# Altium_v0_6_2.net
KiCad netlist of a schematic drawn in Altium Designer
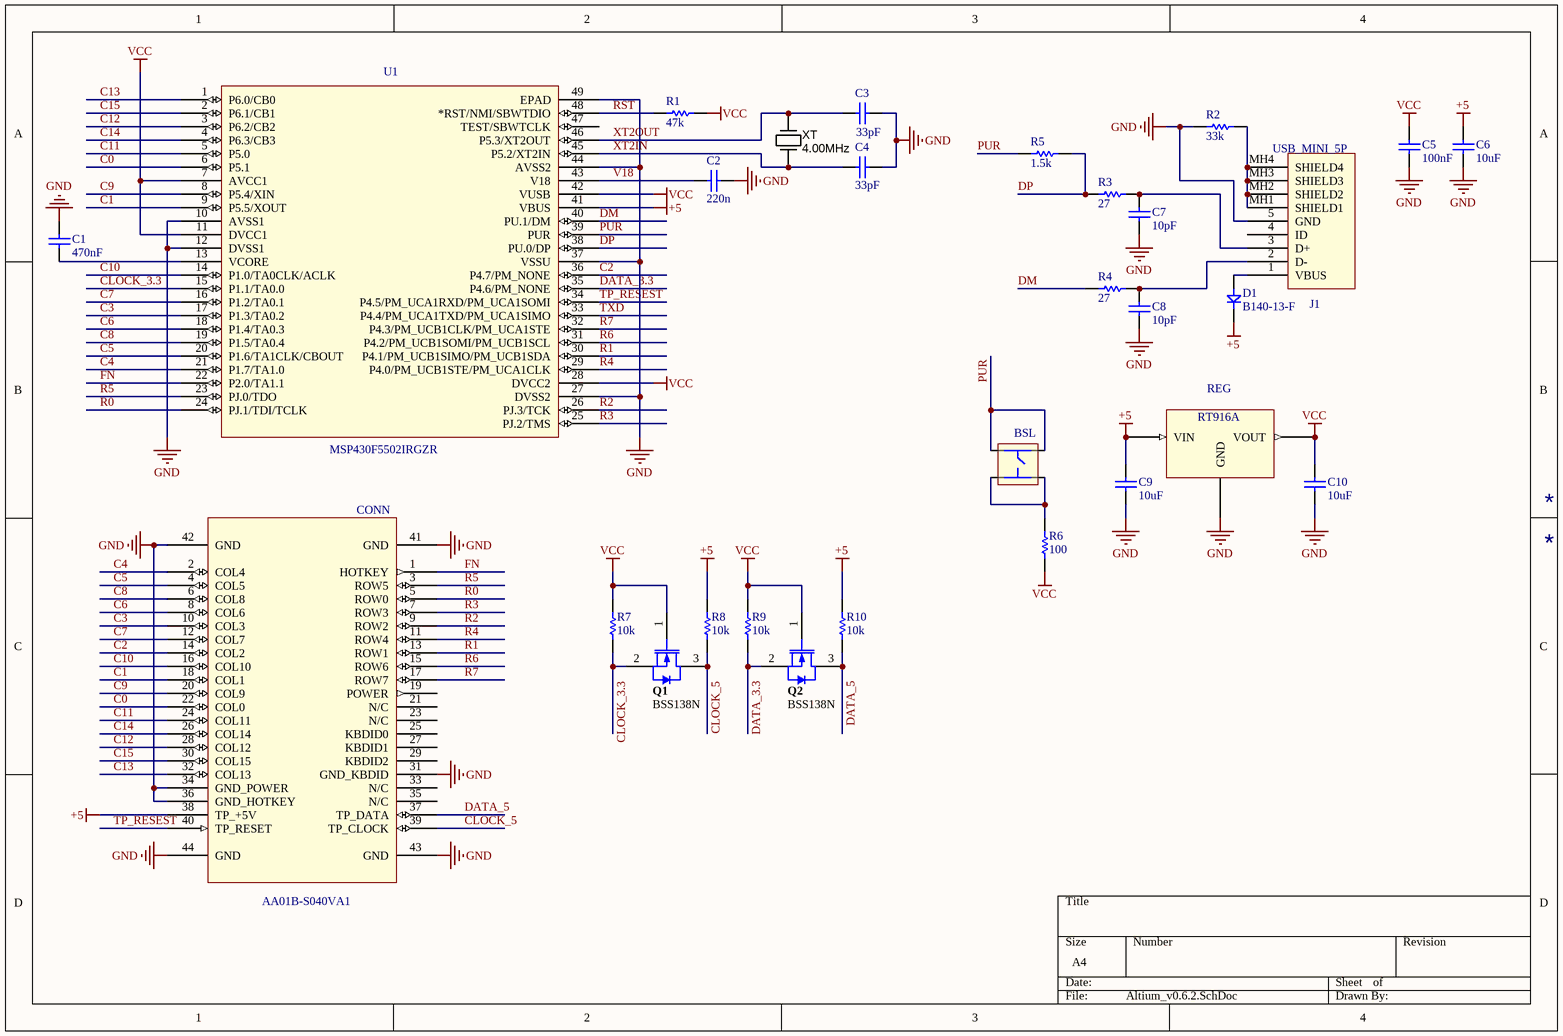
[diagram p0: Altium_v0.6.2.SchDoc]

(export (version "E")
  (design (tool "Eeschema 10.0.6"))
  (components
    (comp (ref "BSL")
      (value "TL3301")
      (footprint "TL3301")
      (description "TL3301, tactile switch, gull wing termination")
      (libsource (lib "MSP430_USB") (part "TL3301"))
    )
    (comp (ref "C1")
      (value "470nF")
      (footprint "C0805")
      (description "Capacitor")
      (fields (field (name "Comment") "Cap") (field (name "PUBLISHER") "Altium Limited"))
      (libsource (lib "Miscellaneous Devices") (part "Cap"))
    )
    (comp (ref "C2")
      (value "220n")
      (footprint "C0805")
      (description "Capacitor")
      (fields (field (name "Comment") "Cap") (field (name "PUBLISHER") "Altium Limited"))
      (libsource (lib "Miscellaneous Devices") (part "Cap"))
    )
    (comp (ref "C3")
      (value "33pF")
      (footprint "C0805")
      (description "Capacitor")
      (fields (field (name "Comment") "Cap") (field (name "PUBLISHER") "Altium Limited"))
      (libsource (lib "Miscellaneous Devices") (part "Cap"))
    )
    (comp (ref "C4")
      (value "33pF")
      (footprint "C0805")
      (description "Capacitor")
      (fields (field (name "Comment") "Cap") (field (name "PUBLISHER") "Altium Limited"))
      (libsource (lib "Miscellaneous Devices") (part "Cap"))
    )
    (comp (ref "C5")
      (value "100nF")
      (description "Capacitor")
      (fields (field (name "Comment") "Cap") (field (name "PUBLISHER") "Altium Limited"))
      (libsource (lib "Miscellaneous Devices") (part "Cap"))
    )
    (comp (ref "C6")
      (value "10uF")
      (description "Capacitor")
      (fields (field (name "Comment") "Cap") (field (name "PUBLISHER") "Altium Limited"))
      (libsource (lib "Miscellaneous Devices") (part "Cap"))
    )
    (comp (ref "C7")
      (value "10pF")
      (description "Capacitor")
      (fields (field (name "Comment") "Cap") (field (name "PUBLISHER") "Altium Limited"))
      (libsource (lib "Miscellaneous Devices") (part "Cap"))
    )
    (comp (ref "C8")
      (value "10pF")
      (description "Capacitor")
      (fields (field (name "Comment") "Cap") (field (name "PUBLISHER") "Altium Limited"))
      (libsource (lib "Miscellaneous Devices") (part "Cap"))
    )
    (comp (ref "C9")
      (value "10uF")
      (description "Capacitor")
      (fields (field (name "Comment") "Cap") (field (name "PUBLISHER") "Altium Limited"))
      (libsource (lib "Miscellaneous Devices") (part "Cap"))
    )
    (comp (ref "C10")
      (value "10uF")
      (description "Capacitor")
      (fields (field (name "Comment") "Cap") (field (name "PUBLISHER") "Altium Limited"))
      (libsource (lib "Miscellaneous Devices") (part "Cap"))
    )
    (comp (ref "CONN")
      (value "AA01B-S040VA1")
      (footprint "AA01B-S040VA1")
      (description "AA01B-S040VA1, LAPTOP KEYBOARD RECEPTACLE")
      (libsource (lib "AA01B-S040VA1") (part "AA01B-S040VA1"))
    )
    (comp (ref "D1")
      (value "B140-13-F")
      (footprint "SMA")
      (description "B140-13-F, Schottky Diode")
      (libsource (lib "MSP430_USB") (part "B140-13-F"))
    )
    (comp (ref "J1")
      (value "USB_MINI_5P")
      (footprint "USB_Mini-B_Molex_SMT")
      (description "Mini USB Connector")
      (libsource (lib "MSP430_USB") (part "USB_MINI_5P"))
    )
    (comp (ref "Q1")
      (value "BSS138N")
      (footprint "INF-PG-SOT23_N")
      (fields (field (name "MANUFACTURER") "Infineon"))
      (libsource (lib "BSS138N") (part "BSS138N"))
    )
    (comp (ref "Q2")
      (value "BSS138N")
      (footprint "INF-PG-SOT23_N")
      (fields (field (name "MANUFACTURER") "Infineon"))
      (libsource (lib "BSS138N") (part "BSS138N"))
    )
    (comp (ref "R1")
      (value "47k")
      (footprint "C0805")
      (description "Resistor")
      (fields (field (name "Comment") "Res1") (field (name "PUBLISHER") "Altium Limited"))
      (libsource (lib "Miscellaneous Devices") (part "Res1"))
    )
    (comp (ref "R2")
      (value "33k")
      (footprint "C0805")
      (description "Resistor")
      (fields (field (name "Comment") "Res1") (field (name "PUBLISHER") "Altium Limited"))
      (libsource (lib "Miscellaneous Devices") (part "Res1"))
    )
    (comp (ref "R3")
      (value "27")
      (description "Resistor")
      (fields (field (name "Comment") "Res1") (field (name "PUBLISHER") "Altium Limited"))
      (libsource (lib "Miscellaneous Devices") (part "Res1"))
    )
    (comp (ref "R4")
      (value "27")
      (description "Resistor")
      (fields (field (name "Comment") "Res1") (field (name "PUBLISHER") "Altium Limited"))
      (libsource (lib "Miscellaneous Devices") (part "Res1"))
    )
    (comp (ref "R5")
      (value "1.5k")
      (footprint "C0805")
      (description "Resistor")
      (fields (field (name "Comment") "Res1") (field (name "PUBLISHER") "Altium Limited"))
      (libsource (lib "Miscellaneous Devices") (part "Res1"))
    )
    (comp (ref "R6")
      (value "100")
      (description "Resistor")
      (fields (field (name "Comment") "Res1") (field (name "PUBLISHER") "Altium Limited"))
      (libsource (lib "Miscellaneous Devices") (part "Res1"))
    )
    (comp (ref "R7")
      (value "10k")
      (description "Resistor")
      (fields (field (name "Comment") "Res1") (field (name "PUBLISHER") "Altium Limited"))
      (libsource (lib "Miscellaneous Devices") (part "Res1"))
    )
    (comp (ref "R8")
      (value "10k")
      (description "Resistor")
      (fields (field (name "Comment") "Res1") (field (name "PUBLISHER") "Altium Limited"))
      (libsource (lib "Miscellaneous Devices") (part "Res1"))
    )
    (comp (ref "R9")
      (value "10k")
      (footprint "C0805")
      (description "Resistor")
      (fields (field (name "Comment") "Res1") (field (name "PUBLISHER") "Altium Limited"))
      (libsource (lib "Miscellaneous Devices") (part "Res1"))
    )
    (comp (ref "R10")
      (value "10k")
      (description "Resistor")
      (fields (field (name "Comment") "Res1") (field (name "PUBLISHER") "Altium Limited"))
      (libsource (lib "Miscellaneous Devices") (part "Res1"))
    )
    (comp (ref "REG")
      (value "RT9164A LDO")
      (footprint "SOT223")
      (description "RT9164-33[P/G]G, 3.3V, LDO")
      (libsource (lib "MSP430_USB") (part "RT9164A LDO"))
    )
    (comp (ref "U1")
      (value "MSP430F5502IRGZR")
      (footprint "RGZ48_5P15X5P15")
      (description "MSP430F5502")
      (fields
        (field (name "MANUFACTURER_PART_NUMBER") "msp430f5502_rgz_48")
        (field (name "MANUFACTURER") "Texas Instruments")
      )
      (libsource (lib "MSP430F5502_RGZ_48") (part "MSP430F5502_RGZ_"))
    )
    (comp (ref "XT")
      (value "4.00MHz")
      (footprint "CRYSTAL_HC49-US-SM")
      (description "Resonator Ceramic 6.00 MHz 30ppm")
      (libsource (lib "PBL - Resonators") (part "Crystal_6MHz_HC49/US"))
    )
  )
  (nets
    (net (code "1") (name "+5") (class "Default")
      (node (ref "C6") (pin "2") (pinfunction "2_2") (pintype "passive"))
      (node (ref "C9") (pin "2") (pinfunction "2_2") (pintype "passive"))
      (node (ref "CONN") (pin "38") (pinfunction "TP_+5V_38") (pintype "power_in"))
      (node (ref "D1") (pin "2") (pinfunction "2_2") (pintype "passive"))
      (node (ref "R10") (pin "2") (pinfunction "2_2") (pintype "passive"))
      (node (ref "R8") (pin "2") (pinfunction "2_2") (pintype "passive"))
      (node (ref "REG") (pin "3") (pinfunction "VIN_3") (pintype "input"))
      (node (ref "U1") (pin "41") (pinfunction "VBUS_41") (pintype "power_in"))
    )
    (net (code "2") (name "/C0") (class "Default")
      (node (ref "CONN") (pin "22") (pinfunction "COL0_22") (pintype "bidirectional"))
      (node (ref "U1") (pin "6") (pinfunction "P5.1_6") (pintype "bidirectional"))
    )
    (net (code "3") (name "/C1") (class "Default")
      (node (ref "CONN") (pin "18") (pinfunction "COL1_18") (pintype "bidirectional"))
      (node (ref "U1") (pin "9") (pinfunction "P5.5/XOUT_9") (pintype "bidirectional"))
    )
    (net (code "4") (name "/C2") (class "Default")
      (node (ref "CONN") (pin "14") (pinfunction "COL2_14") (pintype "bidirectional"))
      (node (ref "U1") (pin "36") (pinfunction "P4.7/PM_NONE_36") (pintype "bidirectional"))
    )
    (net (code "5") (name "/C3") (class "Default")
      (node (ref "CONN") (pin "10") (pinfunction "COL3_10") (pintype "bidirectional"))
      (node (ref "U1") (pin "17") (pinfunction "P1.3/TA0.2_17") (pintype "bidirectional"))
    )
    (net (code "6") (name "/C4") (class "Default")
      (node (ref "CONN") (pin "2") (pinfunction "COL4_2") (pintype "bidirectional"))
      (node (ref "U1") (pin "21") (pinfunction "P1.7/TA1.0_21") (pintype "bidirectional"))
    )
    (net (code "7") (name "/C5") (class "Default")
      (node (ref "CONN") (pin "4") (pinfunction "COL5_4") (pintype "bidirectional"))
      (node (ref "U1") (pin "20") (pinfunction "P1.6/TA1CLK/CBOUT_20") (pintype "bidirectional"))
    )
    (net (code "8") (name "/C6") (class "Default")
      (node (ref "CONN") (pin "8") (pinfunction "COL6_8") (pintype "bidirectional"))
      (node (ref "U1") (pin "18") (pinfunction "P1.4/TA0.3_18") (pintype "bidirectional"))
    )
    (net (code "9") (name "/C7") (class "Default")
      (node (ref "CONN") (pin "12") (pinfunction "COL7_12") (pintype "bidirectional"))
      (node (ref "U1") (pin "16") (pinfunction "P1.2/TA0.1_16") (pintype "bidirectional"))
    )
    (net (code "10") (name "/C8") (class "Default")
      (node (ref "CONN") (pin "6") (pinfunction "COL8_6") (pintype "bidirectional"))
      (node (ref "U1") (pin "19") (pinfunction "P1.5/TA0.4_19") (pintype "bidirectional"))
    )
    (net (code "11") (name "/C9") (class "Default")
      (node (ref "CONN") (pin "20") (pinfunction "COL9_20") (pintype "bidirectional"))
      (node (ref "U1") (pin "8") (pinfunction "P5.4/XIN_8") (pintype "bidirectional"))
    )
    (net (code "12") (name "/C10") (class "Default")
      (node (ref "CONN") (pin "16") (pinfunction "COL10_16") (pintype "bidirectional"))
      (node (ref "U1") (pin "14") (pinfunction "P1.0/TA0CLK/ACLK_14") (pintype "bidirectional"))
    )
    (net (code "13") (name "/C11") (class "Default")
      (node (ref "CONN") (pin "24") (pinfunction "COL11_24") (pintype "bidirectional"))
      (node (ref "U1") (pin "5") (pinfunction "P5.0_5") (pintype "bidirectional"))
    )
    (net (code "14") (name "/C12") (class "Default")
      (node (ref "CONN") (pin "28") (pinfunction "COL12_28") (pintype "bidirectional"))
      (node (ref "U1") (pin "3") (pinfunction "P6.2/CB2_3") (pintype "bidirectional"))
    )
    (net (code "15") (name "/C13") (class "Default")
      (node (ref "CONN") (pin "32") (pinfunction "COL13_32") (pintype "bidirectional"))
      (node (ref "U1") (pin "1") (pinfunction "P6.0/CB0_1") (pintype "bidirectional"))
    )
    (net (code "16") (name "/C14") (class "Default")
      (node (ref "CONN") (pin "26") (pinfunction "COL14_26") (pintype "bidirectional"))
      (node (ref "U1") (pin "4") (pinfunction "P6.3/CB3_4") (pintype "bidirectional"))
    )
    (net (code "17") (name "/C15") (class "Default")
      (node (ref "CONN") (pin "30") (pinfunction "COL15_30") (pintype "bidirectional"))
      (node (ref "U1") (pin "2") (pinfunction "P6.1/CB1_2") (pintype "bidirectional"))
    )
    (net (code "18") (name "/CLOCK_3.3") (class "Default")
      (node (ref "Q1") (pin "2") (pinfunction "SOURCE_2") (pintype "passive"))
      (node (ref "R7") (pin "1") (pinfunction "1_1") (pintype "passive"))
      (node (ref "U1") (pin "15") (pinfunction "P1.1/TA0.0_15") (pintype "bidirectional"))
    )
    (net (code "19") (name "/CLOCK_5") (class "Default")
      (node (ref "CONN") (pin "39") (pinfunction "TP_CLOCK_39") (pintype "bidirectional"))
      (node (ref "Q1") (pin "3") (pinfunction "DRAIN_3") (pintype "passive"))
      (node (ref "R8") (pin "1") (pinfunction "1_1") (pintype "passive"))
    )
    (net (code "20") (name "/DATA_3.3") (class "Default")
      (node (ref "Q2") (pin "2") (pinfunction "SOURCE_2") (pintype "passive"))
      (node (ref "R9") (pin "1") (pinfunction "1_1") (pintype "passive"))
      (node (ref "U1") (pin "35") (pinfunction "P4.6/PM_NONE_35") (pintype "bidirectional"))
    )
    (net (code "21") (name "/DATA_5") (class "Default")
      (node (ref "CONN") (pin "37") (pinfunction "TP_DATA_37") (pintype "bidirectional"))
      (node (ref "Q2") (pin "3") (pinfunction "DRAIN_3") (pintype "passive"))
      (node (ref "R10") (pin "1") (pinfunction "1_1") (pintype "passive"))
    )
    (net (code "22") (name "/DM") (class "Default")
      (node (ref "R4") (pin "1") (pinfunction "1_1") (pintype "passive"))
      (node (ref "U1") (pin "40") (pinfunction "PU.1/DM_40") (pintype "bidirectional"))
    )
    (net (code "23") (name "/DP") (class "Default")
      (node (ref "R3") (pin "1") (pinfunction "1_1") (pintype "passive"))
      (node (ref "R5") (pin "2") (pinfunction "2_2") (pintype "passive"))
      (node (ref "U1") (pin "38") (pinfunction "PU.0/DP_38") (pintype "bidirectional"))
    )
    (net (code "24") (name "/FN") (class "Default")
      (node (ref "CONN") (pin "1") (pinfunction "HOTKEY_1") (pintype "output"))
      (node (ref "U1") (pin "22") (pinfunction "P2.0/TA1.1_22") (pintype "bidirectional"))
    )
    (net (code "25") (name "/PUR") (class "Default")
      (node (ref "BSL") (pin "1") (pinfunction "1_1") (pintype "passive"))
      (node (ref "BSL") (pin "2") (pinfunction "2_2") (pintype "passive"))
      (node (ref "R5") (pin "1") (pinfunction "1_1") (pintype "passive"))
      (node (ref "U1") (pin "39") (pinfunction "PUR_39") (pintype "bidirectional"))
    )
    (net (code "26") (name "/R0") (class "Default")
      (node (ref "CONN") (pin "5") (pinfunction "ROW0_5") (pintype "bidirectional"))
      (node (ref "U1") (pin "24") (pinfunction "PJ.1/TDI/TCLK_24") (pintype "bidirectional"))
    )
    (net (code "27") (name "/R1") (class "Default")
      (node (ref "CONN") (pin "13") (pinfunction "ROW1_13") (pintype "bidirectional"))
      (node (ref "U1") (pin "30") (pinfunction "P4.1/PM_UCB1SIMO/PM_UCB1SDA_30") (pintype "bidirectional"))
    )
    (net (code "28") (name "/R2") (class "Default")
      (node (ref "CONN") (pin "9") (pinfunction "ROW2_9") (pintype "bidirectional"))
      (node (ref "U1") (pin "26") (pinfunction "PJ.3/TCK_26") (pintype "bidirectional"))
    )
    (net (code "29") (name "/R3") (class "Default")
      (node (ref "CONN") (pin "7") (pinfunction "ROW3_7") (pintype "bidirectional"))
      (node (ref "U1") (pin "25") (pinfunction "PJ.2/TMS_25") (pintype "bidirectional"))
    )
    (net (code "30") (name "/R4") (class "Default")
      (node (ref "CONN") (pin "11") (pinfunction "ROW4_11") (pintype "bidirectional"))
      (node (ref "U1") (pin "29") (pinfunction "P4.0/PM_UCB1STE/PM_UCA1CLK_29") (pintype "bidirectional"))
    )
    (net (code "31") (name "/R5") (class "Default")
      (node (ref "CONN") (pin "3") (pinfunction "ROW5_3") (pintype "bidirectional"))
      (node (ref "U1") (pin "23") (pinfunction "PJ.0/TDO_23") (pintype "bidirectional"))
    )
    (net (code "32") (name "/R6") (class "Default")
      (node (ref "CONN") (pin "15") (pinfunction "ROW6_15") (pintype "bidirectional"))
      (node (ref "U1") (pin "31") (pinfunction "P4.2/PM_UCB1SOMI/PM_UCB1SCL_31") (pintype "bidirectional"))
    )
    (net (code "33") (name "/R7") (class "Default")
      (node (ref "CONN") (pin "17") (pinfunction "ROW7_17") (pintype "bidirectional"))
      (node (ref "U1") (pin "32") (pinfunction "P4.3/PM_UCB1CLK/PM_UCA1STE_32") (pintype "bidirectional"))
    )
    (net (code "34") (name "/RST") (class "Default")
      (node (ref "R1") (pin "1") (pinfunction "1_1") (pintype "passive"))
      (node (ref "U1") (pin "48") (pinfunction "*RST/NMI/SBWTDIO_48") (pintype "bidirectional"))
    )
    (net (code "35") (name "/TP_RESEST") (class "Default")
      (node (ref "CONN") (pin "40") (pinfunction "TP_RESET_40") (pintype "input"))
      (node (ref "U1") (pin "34") (pinfunction "P4.5/PM_UCA1RXD/PM_UCA1SOMI_34") (pintype "bidirectional"))
    )
    (net (code "36") (name "/TXD") (class "Default")
      (node (ref "U1") (pin "33") (pinfunction "P4.4/PM_UCA1TXD/PM_UCA1SIMO_33") (pintype "bidirectional"))
    )
    (net (code "37") (name "/V18") (class "Default")
      (node (ref "C2") (pin "2") (pinfunction "2_2") (pintype "passive"))
      (node (ref "U1") (pin "43") (pinfunction "V18_43") (pintype "power_in"))
    )
    (net (code "38") (name "/XT2IN") (class "Default")
      (node (ref "C4") (pin "1") (pinfunction "1_1") (pintype "passive"))
      (node (ref "U1") (pin "45") (pinfunction "P5.2/XT2IN_45") (pintype "bidirectional"))
      (node (ref "XT") (pin "1") (pinfunction "IN_1") (pintype "passive"))
    )
    (net (code "39") (name "/XT2OUT") (class "Default")
      (node (ref "C3") (pin "2") (pinfunction "2_2") (pintype "passive"))
      (node (ref "U1") (pin "46") (pinfunction "P5.3/XT2OUT_46") (pintype "bidirectional"))
      (node (ref "XT") (pin "2") (pinfunction "OUT_2") (pintype "passive"))
    )
    (net (code "40") (name "GND") (class "Default")
      (node (ref "C1") (pin "2") (pinfunction "2_2") (pintype "passive"))
      (node (ref "C10") (pin "1") (pinfunction "1_1") (pintype "passive"))
      (node (ref "C2") (pin "1") (pinfunction "1_1") (pintype "passive"))
      (node (ref "C3") (pin "1") (pinfunction "1_1") (pintype "passive"))
      (node (ref "C4") (pin "2") (pinfunction "2_2") (pintype "passive"))
      (node (ref "C5") (pin "1") (pinfunction "1_1") (pintype "passive"))
      (node (ref "C6") (pin "1") (pinfunction "1_1") (pintype "passive"))
      (node (ref "C7") (pin "1") (pinfunction "1_1") (pintype "passive"))
      (node (ref "C8") (pin "1") (pinfunction "1_1") (pintype "passive"))
      (node (ref "C9") (pin "1") (pinfunction "1_1") (pintype "passive"))
      (node (ref "CONN") (pin "31") (pinfunction "GND_KBDID_31") (pintype "passive"))
      (node (ref "CONN") (pin "34") (pinfunction "GND_POWER_34") (pintype "power_in"))
      (node (ref "CONN") (pin "36") (pinfunction "GND_HOTKEY_36") (pintype "passive"))
      (node (ref "CONN") (pin "41") (pinfunction "GND_41") (pintype "passive"))
      (node (ref "CONN") (pin "42") (pinfunction "GND_42") (pintype "passive"))
      (node (ref "CONN") (pin "43") (pinfunction "GND_43") (pintype "passive"))
      (node (ref "CONN") (pin "44") (pinfunction "GND_44") (pintype "passive"))
      (node (ref "J1") (pin "5") (pinfunction "GND_5") (pintype "passive"))
      (node (ref "R2") (pin "2") (pinfunction "2_2") (pintype "passive"))
      (node (ref "REG") (pin "1") (pinfunction "GND_1") (pintype "passive"))
      (node (ref "U1") (pin "10") (pinfunction "AVSS1_10") (pintype "power_in"))
      (node (ref "U1") (pin "12") (pinfunction "DVSS1_12") (pintype "power_in"))
      (node (ref "U1") (pin "27") (pinfunction "DVSS2_27") (pintype "power_in"))
      (node (ref "U1") (pin "37") (pinfunction "VSSU_37") (pintype "power_in"))
      (node (ref "U1") (pin "44") (pinfunction "AVSS2_44") (pintype "power_in"))
      (node (ref "U1") (pin "49") (pinfunction "EPAD_49") (pintype "passive"))
    )
    (net (code "41") (name "Net-(BSL-Pad3)") (class "Default")
      (node (ref "BSL") (pin "3") (pinfunction "3_3") (pintype "passive"))
      (node (ref "BSL") (pin "4") (pinfunction "4_4") (pintype "passive"))
      (node (ref "R6") (pin "2") (pinfunction "2_2") (pintype "passive"))
    )
    (net (code "42") (name "Net-(J1-D+)") (class "Default")
      (node (ref "C7") (pin "2") (pinfunction "2_2") (pintype "passive"))
      (node (ref "J1") (pin "3") (pinfunction "D+_3") (pintype "passive"))
      (node (ref "R3") (pin "2") (pinfunction "2_2") (pintype "passive"))
    )
    (net (code "43") (name "Net-(J1-D-)") (class "Default")
      (node (ref "C8") (pin "2") (pinfunction "2_2") (pintype "passive"))
      (node (ref "J1") (pin "2") (pinfunction "D-_2") (pintype "passive"))
      (node (ref "R4") (pin "2") (pinfunction "2_2") (pintype "passive"))
    )
    (net (code "44") (name "Net-(J1-SHIELD1)") (class "Default")
      (node (ref "J1") (pin "MH1") (pinfunction "SHIELD1_MH1") (pintype "passive"))
      (node (ref "J1") (pin "MH2") (pinfunction "SHIELD2_MH2") (pintype "passive"))
      (node (ref "J1") (pin "MH3") (pinfunction "SHIELD3_MH3") (pintype "passive"))
      (node (ref "J1") (pin "MH4") (pinfunction "SHIELD4_MH4") (pintype "passive"))
      (node (ref "R2") (pin "1") (pinfunction "1_1") (pintype "passive"))
    )
    (net (code "45") (name "Net-(J1-VBUS)") (class "Default")
      (node (ref "D1") (pin "1") (pinfunction "1_1") (pintype "passive"))
      (node (ref "J1") (pin "1") (pinfunction "VBUS_1") (pintype "passive"))
    )
    (net (code "46") (name "Net-(U1-VCORE)") (class "Default")
      (node (ref "C1") (pin "1") (pinfunction "1_1") (pintype "passive"))
      (node (ref "U1") (pin "13") (pinfunction "VCORE_13") (pintype "power_in"))
    )
    (net (code "47") (name "VCC") (class "Default")
      (node (ref "C10") (pin "2") (pinfunction "2_2") (pintype "passive"))
      (node (ref "C5") (pin "2") (pinfunction "2_2") (pintype "passive"))
      (node (ref "Q1") (pin "1") (pinfunction "GATE_1") (pintype "passive"))
      (node (ref "Q2") (pin "1") (pinfunction "GATE_1") (pintype "passive"))
      (node (ref "R1") (pin "2") (pinfunction "2_2") (pintype "passive"))
      (node (ref "R6") (pin "1") (pinfunction "1_1") (pintype "passive"))
      (node (ref "R7") (pin "2") (pinfunction "2_2") (pintype "passive"))
      (node (ref "R9") (pin "2") (pinfunction "2_2") (pintype "passive"))
      (node (ref "REG") (pin "2") (pinfunction "VOUT_2") (pintype "output"))
      (node (ref "U1") (pin "11") (pinfunction "DVCC1_11") (pintype "power_in"))
      (node (ref "U1") (pin "28") (pinfunction "DVCC2_28") (pintype "power_in"))
      (node (ref "U1") (pin "42") (pinfunction "VUSB_42") (pintype "power_in"))
      (node (ref "U1") (pin "7") (pinfunction "AVCC1_7") (pintype "power_in"))
    )
    (net (code "48") (name "unconnected-(CONN-KBDID0-Pad25)") (class "Default")
      (node (ref "CONN") (pin "25") (pinfunction "KBDID0_25") (pintype "passive"))
    )
    (net (code "49") (name "unconnected-(CONN-KBDID1-Pad27)") (class "Default")
      (node (ref "CONN") (pin "27") (pinfunction "KBDID1_27") (pintype "passive"))
    )
    (net (code "50") (name "unconnected-(CONN-KBDID2-Pad29)") (class "Default")
      (node (ref "CONN") (pin "29") (pinfunction "KBDID2_29") (pintype "passive"))
    )
    (net (code "51") (name "unconnected-(CONN-N{slash}C-Pad21)") (class "Default")
      (node (ref "CONN") (pin "21") (pinfunction "N/C_21") (pintype "passive"))
    )
    (net (code "52") (name "unconnected-(CONN-N{slash}C-Pad23)") (class "Default")
      (node (ref "CONN") (pin "23") (pinfunction "N/C_23") (pintype "passive"))
    )
    (net (code "53") (name "unconnected-(CONN-N{slash}C-Pad33)") (class "Default")
      (node (ref "CONN") (pin "33") (pinfunction "N/C_33") (pintype "passive"))
    )
    (net (code "54") (name "unconnected-(CONN-N{slash}C-Pad35)") (class "Default")
      (node (ref "CONN") (pin "35") (pinfunction "N/C_35") (pintype "passive"))
    )
    (net (code "55") (name "unconnected-(CONN-POWER-Pad19)") (class "Default")
      (node (ref "CONN") (pin "19") (pinfunction "POWER_19") (pintype "output"))
    )
    (net (code "56") (name "unconnected-(J1-ID-Pad4)") (class "Default")
      (node (ref "J1") (pin "4") (pinfunction "ID_4") (pintype "passive"))
    )
    (net (code "57") (name "unconnected-(U1-TEST{slash}SBWTCLK-Pad47)") (class "Default")
      (node (ref "U1") (pin "47") (pinfunction "TEST/SBWTCLK_47") (pintype "bidirectional"))
    )
  )
)
